# wifi.net
KiCad netlist of a schematic drawn in Altium Designer
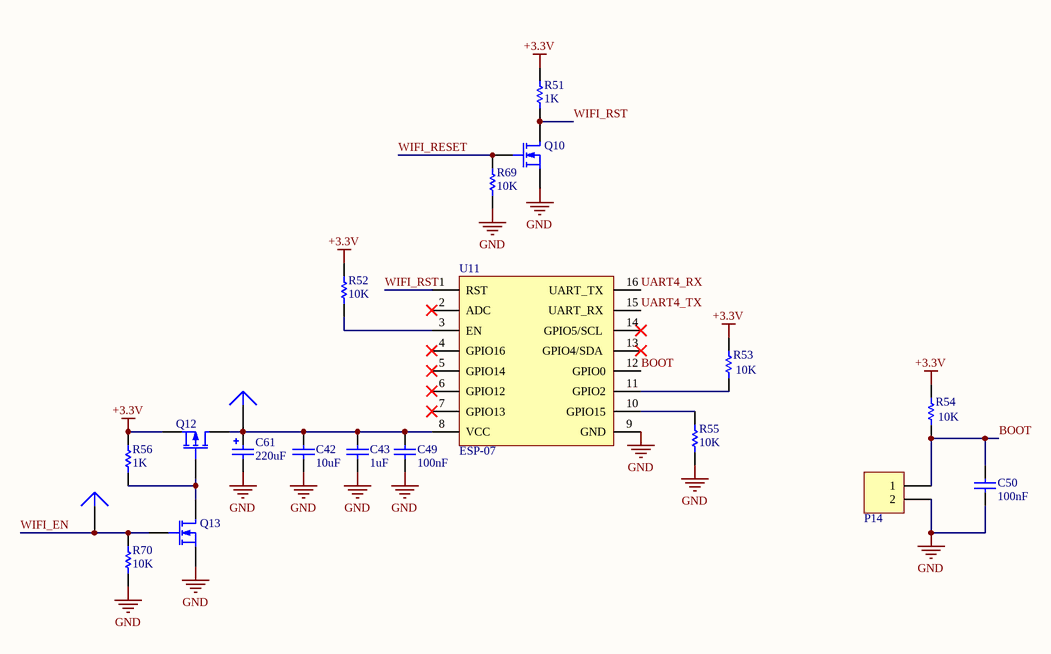
[diagram p0: wifi.SchDoc]

(export (version "E")
  (design (tool "Eeschema 10.0.6"))
  (components
    (comp (ref "C42")
      (value "10uF")
      (footprint "C0402")
      (description "Capacitor")
      (fields (field (name "Comment") "Cap 10uF"))
      (libsource (lib "integratedLib") (part "Cap 10uF"))
    )
    (comp (ref "C43")
      (value "1uF")
      (footprint "C0402")
      (description "Capacitor")
      (fields (field (name "Comment") "Cap 1uF"))
      (libsource (lib "integratedLib") (part "Cap 1uF"))
    )
    (comp (ref "C49")
      (value "100nF")
      (footprint "C0402")
      (description "Capacitor")
      (fields (field (name "Comment") "Cap 100nF"))
      (libsource (lib "integratedLib") (part "Cap 100nF"))
    )
    (comp (ref "C50")
      (value "100nF")
      (footprint "C0402")
      (description "Capacitor")
      (fields (field (name "Comment") "Cap 100nF"))
      (libsource (lib "integratedLib") (part "Cap 100nF"))
    )
    (comp (ref "C61")
      (value "220uF")
      (footprint "CAP-D")
      (description "Polarized Tantalum Capacitor")
      (fields (field (name "Comment") "Tantalum 220uF"))
      (libsource (lib "integratedLib") (part "Tantalum 220uF"))
    )
    (comp (ref "P14")
      (value "Header 2")
      (footprint "HDR1X2")
      (description "Header, 2-Pin")
      (fields (field (name "PUBLISHER") "Altium Limited"))
      (libsource (lib "integratedLib") (part "Header 2"))
    )
    (comp (ref "P25")
      (value "Plug")
      (footprint "pin smd")
      (fields (field (name "PUBLISHER") "Altium Limited"))
      (libsource (lib "integratedLib") (part "Plug"))
    )
    (comp (ref "P29")
      (value "Plug")
      (footprint "pin smd")
      (fields (field (name "PUBLISHER") "Altium Limited"))
      (libsource (lib "integratedLib") (part "Plug"))
    )
    (comp (ref "Q10")
      (value "AO3400A")
      (footprint "SOT23")
      (description "N-MOSFET AO3400A")
      (fields (field (name "PUBLISHER") "Altium Limited"))
      (libsource (lib "integratedLib") (part "MOSFET-N"))
    )
    (comp (ref "Q12")
      (value "AO3401A")
      (footprint "SOT23")
      (description "P-Channel MOSFET AO3401A")
      (fields (field (name "PUBLISHER") "Altium Limited"))
      (libsource (lib "integratedLib") (part "MOSFET-P"))
    )
    (comp (ref "Q13")
      (value "AO3400A")
      (footprint "SOT23")
      (description "N-MOSFET AO3400A")
      (fields (field (name "PUBLISHER") "Altium Limited"))
      (libsource (lib "integratedLib") (part "MOSFET-N"))
    )
    (comp (ref "R51")
      (value "1K")
      (footprint "R0402")
      (description "Resistor")
      (fields (field (name "Comment") "Res_1K"))
      (libsource (lib "integratedLib") (part "Res_1K"))
    )
    (comp (ref "R52")
      (value "10K")
      (footprint "R0402")
      (description "Resistor")
      (fields (field (name "Comment") "Res_10K"))
      (libsource (lib "integratedLib") (part "Res_10K"))
    )
    (comp (ref "R53")
      (value "10K")
      (footprint "R0402")
      (description "Resistor")
      (fields (field (name "Comment") "Res_10K"))
      (libsource (lib "integratedLib") (part "Res_10K"))
    )
    (comp (ref "R54")
      (value "10K")
      (footprint "R0402")
      (description "Resistor")
      (fields (field (name "Comment") "Res_10K"))
      (libsource (lib "integratedLib") (part "Res_10K"))
    )
    (comp (ref "R55")
      (value "10K")
      (footprint "R0402")
      (description "Resistor")
      (fields (field (name "Comment") "Res_10K"))
      (libsource (lib "integratedLib") (part "Res_10K"))
    )
    (comp (ref "R56")
      (value "1K")
      (footprint "R0402")
      (description "Resistor")
      (fields (field (name "Comment") "Res_1K"))
      (libsource (lib "integratedLib") (part "Res_1K"))
    )
    (comp (ref "R69")
      (value "10K")
      (footprint "R0402")
      (description "Resistor")
      (fields (field (name "Comment") "Res_10K"))
      (libsource (lib "integratedLib") (part "Res_10K"))
    )
    (comp (ref "R70")
      (value "10K")
      (footprint "R0402")
      (description "Resistor")
      (fields (field (name "Comment") "Res_10K"))
      (libsource (lib "integratedLib") (part "Res_10K"))
    )
    (comp (ref "U11")
      (value "ESP-07")
      (footprint "ESP-07")
      (description "AiThinker ESP-07")
      (libsource (lib "integratedLib") (part "ESP-07"))
    )
  )
  (nets
    (net (code "1") (name "+3.3V") (class "Default")
      (node (ref "Q12") (pin "2") (pinfunction "S_2") (pintype "passive"))
      (node (ref "R51") (pin "2") (pinfunction "2_2") (pintype "passive"))
      (node (ref "R52") (pin "2") (pinfunction "2_2") (pintype "passive"))
      (node (ref "R53") (pin "2") (pinfunction "2_2") (pintype "passive"))
      (node (ref "R54") (pin "2") (pinfunction "2_2") (pintype "passive"))
      (node (ref "R56") (pin "2") (pinfunction "2_2") (pintype "passive"))
    )
    (net (code "2") (name "/BOOT") (class "Default")
      (node (ref "C50") (pin "2") (pinfunction "2_2") (pintype "passive"))
      (node (ref "P14") (pin "1") (pinfunction "1_1") (pintype "passive"))
      (node (ref "R54") (pin "1") (pinfunction "1_1") (pintype "passive"))
      (node (ref "U11") (pin "12") (pinfunction "GPIO0_12") (pintype "passive"))
    )
    (net (code "3") (name "/UART4_RX") (class "Default")
      (node (ref "U11") (pin "16") (pinfunction "UART_TX_16") (pintype "passive"))
    )
    (net (code "4") (name "/UART4_TX") (class "Default")
      (node (ref "U11") (pin "15") (pinfunction "UART_RX_15") (pintype "passive"))
    )
    (net (code "5") (name "/WIFI_EN") (class "Default")
      (node (ref "P29") (pin "1") (pinfunction "1_1") (pintype "passive"))
      (node (ref "Q13") (pin "1") (pinfunction "G_1") (pintype "passive"))
      (node (ref "R70") (pin "2") (pinfunction "2_2") (pintype "passive"))
    )
    (net (code "6") (name "/WIFI_RESET") (class "Default")
      (node (ref "Q10") (pin "1") (pinfunction "G_1") (pintype "passive"))
      (node (ref "R69") (pin "2") (pinfunction "2_2") (pintype "passive"))
    )
    (net (code "7") (name "/WIFI_RST") (class "Default")
      (node (ref "Q10") (pin "3") (pinfunction "D_3") (pintype "passive"))
      (node (ref "R51") (pin "1") (pinfunction "1_1") (pintype "passive"))
      (node (ref "U11") (pin "1") (pinfunction "RST_1") (pintype "passive"))
    )
    (net (code "8") (name "GND") (class "Default")
      (node (ref "C42") (pin "1") (pinfunction "1_1") (pintype "passive"))
      (node (ref "C43") (pin "1") (pinfunction "1_1") (pintype "passive"))
      (node (ref "C49") (pin "1") (pinfunction "1_1") (pintype "passive"))
      (node (ref "C50") (pin "1") (pinfunction "1_1") (pintype "passive"))
      (node (ref "C61") (pin "1") (pinfunction "1_1") (pintype "passive"))
      (node (ref "P14") (pin "2") (pinfunction "2_2") (pintype "passive"))
      (node (ref "Q10") (pin "2") (pinfunction "S_2") (pintype "passive"))
      (node (ref "Q13") (pin "2") (pinfunction "S_2") (pintype "passive"))
      (node (ref "R55") (pin "1") (pinfunction "1_1") (pintype "passive"))
      (node (ref "R69") (pin "1") (pinfunction "1_1") (pintype "passive"))
      (node (ref "R70") (pin "1") (pinfunction "1_1") (pintype "passive"))
      (node (ref "U11") (pin "9") (pinfunction "GND_9") (pintype "passive"))
    )
    (net (code "9") (name "Net-(Q12-D)") (class "Default")
      (node (ref "C42") (pin "2") (pinfunction "2_2") (pintype "passive"))
      (node (ref "C43") (pin "2") (pinfunction "2_2") (pintype "passive"))
      (node (ref "C49") (pin "2") (pinfunction "2_2") (pintype "passive"))
      (node (ref "C61") (pin "2") (pinfunction "2_2") (pintype "passive"))
      (node (ref "P25") (pin "1") (pinfunction "1_1") (pintype "passive"))
      (node (ref "Q12") (pin "3") (pinfunction "D_3") (pintype "passive"))
      (node (ref "U11") (pin "8") (pinfunction "VCC_8") (pintype "power_in"))
    )
    (net (code "10") (name "Net-(Q12-G)") (class "Default")
      (node (ref "Q12") (pin "1") (pinfunction "G_1") (pintype "passive"))
      (node (ref "Q13") (pin "3") (pinfunction "D_3") (pintype "passive"))
      (node (ref "R56") (pin "1") (pinfunction "1_1") (pintype "passive"))
    )
    (net (code "11") (name "Net-(U11-EN)") (class "Default")
      (node (ref "R52") (pin "1") (pinfunction "1_1") (pintype "passive"))
      (node (ref "U11") (pin "3") (pinfunction "EN_3") (pintype "passive"))
    )
    (net (code "12") (name "Net-(U11-GPIO2)") (class "Default")
      (node (ref "R53") (pin "1") (pinfunction "1_1") (pintype "passive"))
      (node (ref "U11") (pin "11") (pinfunction "GPIO2_11") (pintype "passive"))
    )
    (net (code "13") (name "Net-(U11-GPIO15)") (class "Default")
      (node (ref "R55") (pin "2") (pinfunction "2_2") (pintype "passive"))
      (node (ref "U11") (pin "10") (pinfunction "GPIO15_10") (pintype "passive"))
    )
    (net (code "14") (name "unconnected-(U11-ADC-Pad2)") (class "Default")
      (node (ref "U11") (pin "2") (pinfunction "ADC_2") (pintype "passive+no_connect"))
    )
    (net (code "15") (name "unconnected-(U11-GPIO4{slash}SDA-Pad13)") (class "Default")
      (node (ref "U11") (pin "13") (pinfunction "GPIO4/SDA_13") (pintype "passive+no_connect"))
    )
    (net (code "16") (name "unconnected-(U11-GPIO5{slash}SCL-Pad14)") (class "Default")
      (node (ref "U11") (pin "14") (pinfunction "GPIO5/SCL_14") (pintype "passive+no_connect"))
    )
    (net (code "17") (name "unconnected-(U11-GPIO12-Pad6)") (class "Default")
      (node (ref "U11") (pin "6") (pinfunction "GPIO12_6") (pintype "passive+no_connect"))
    )
    (net (code "18") (name "unconnected-(U11-GPIO13-Pad7)") (class "Default")
      (node (ref "U11") (pin "7") (pinfunction "GPIO13_7") (pintype "passive+no_connect"))
    )
    (net (code "19") (name "unconnected-(U11-GPIO14-Pad5)") (class "Default")
      (node (ref "U11") (pin "5") (pinfunction "GPIO14_5") (pintype "passive+no_connect"))
    )
    (net (code "20") (name "unconnected-(U11-GPIO16-Pad4)") (class "Default")
      (node (ref "U11") (pin "4") (pinfunction "GPIO16_4") (pintype "passive+no_connect"))
    )
  )
)
